# Sheet2.net
KiCad netlist of a schematic drawn in Altium Designer
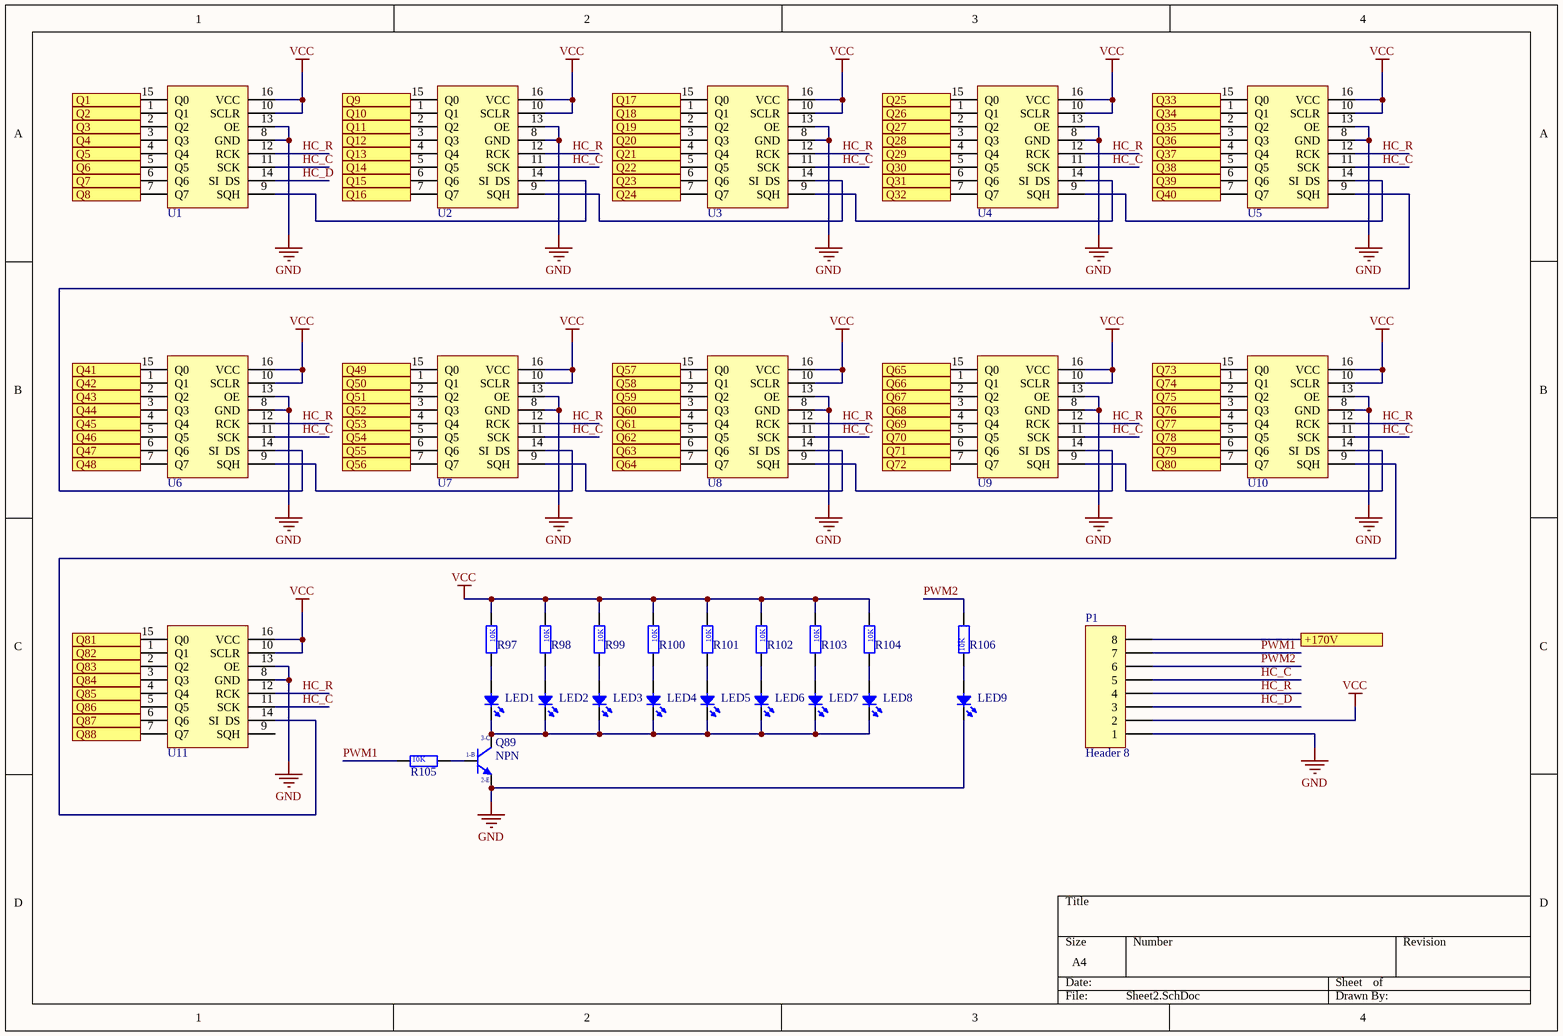
[diagram p0: Sheet2.SchDoc]

(export (version "E")
  (design (tool "Eeschema 10.0.6"))
  (components
    (comp (ref "LED1")
      (value "LED")
      (footprint "0805D")
      (fields (field (name "PUBLISHER") "Altium Limited"))
      (libsource (lib "吴原理图库") (part "LED"))
    )
    (comp (ref "LED2")
      (value "LED")
      (footprint "0805D")
      (fields (field (name "PUBLISHER") "Altium Limited"))
      (libsource (lib "吴原理图库") (part "LED"))
    )
    (comp (ref "LED3")
      (value "LED")
      (footprint "0805D")
      (fields (field (name "PUBLISHER") "Altium Limited"))
      (libsource (lib "吴原理图库") (part "LED"))
    )
    (comp (ref "LED4")
      (value "LED")
      (footprint "0805D")
      (fields (field (name "PUBLISHER") "Altium Limited"))
      (libsource (lib "吴原理图库") (part "LED"))
    )
    (comp (ref "LED5")
      (value "LED")
      (footprint "0805D")
      (fields (field (name "PUBLISHER") "Altium Limited"))
      (libsource (lib "吴原理图库") (part "LED"))
    )
    (comp (ref "LED6")
      (value "LED")
      (footprint "0805D")
      (fields (field (name "PUBLISHER") "Altium Limited"))
      (libsource (lib "吴原理图库") (part "LED"))
    )
    (comp (ref "LED7")
      (value "LED")
      (footprint "0805D")
      (fields (field (name "PUBLISHER") "Altium Limited"))
      (libsource (lib "吴原理图库") (part "LED"))
    )
    (comp (ref "LED8")
      (value "LED")
      (footprint "0805D")
      (fields (field (name "PUBLISHER") "Altium Limited"))
      (libsource (lib "吴原理图库") (part "LED"))
    )
    (comp (ref "LED9")
      (value "LED")
      (footprint "0805D")
      (fields (field (name "PUBLISHER") "Altium Limited"))
      (libsource (lib "吴原理图库") (part "LED"))
    )
    (comp (ref "P1")
      (value "Header 8")
      (footprint "HDR1X8")
      (description "Header, 8-Pin")
      (fields (field (name "PUBLISHER") "Altium Limited"))
      (libsource (lib "Miscellaneous Connectors") (part "Header 8"))
    )
    (comp (ref "Q89") (value "NPN") (footprint "SOT-23") (libsource (lib "吴原理图库") (part "NPN-S8050-SOT-23")))
    (comp (ref "R97")
      (value "10K")
      (footprint "0805")
      (fields (field (name "Comment") "R"))
      (libsource (lib "吴原理图库") (part "R"))
    )
    (comp (ref "R98")
      (value "10K")
      (footprint "0805")
      (fields (field (name "Comment") "R"))
      (libsource (lib "吴原理图库") (part "R"))
    )
    (comp (ref "R99")
      (value "10K")
      (footprint "0805")
      (fields (field (name "Comment") "R"))
      (libsource (lib "吴原理图库") (part "R"))
    )
    (comp (ref "R100")
      (value "10K")
      (footprint "0805")
      (fields (field (name "Comment") "R"))
      (libsource (lib "吴原理图库") (part "R"))
    )
    (comp (ref "R101")
      (value "10K")
      (footprint "0805")
      (fields (field (name "Comment") "R"))
      (libsource (lib "吴原理图库") (part "R"))
    )
    (comp (ref "R102")
      (value "10K")
      (footprint "0805")
      (fields (field (name "Comment") "R"))
      (libsource (lib "吴原理图库") (part "R"))
    )
    (comp (ref "R103")
      (value "10K")
      (footprint "0805")
      (fields (field (name "Comment") "R"))
      (libsource (lib "吴原理图库") (part "R"))
    )
    (comp (ref "R104")
      (value "10K")
      (footprint "0805")
      (fields (field (name "Comment") "R"))
      (libsource (lib "吴原理图库") (part "R"))
    )
    (comp (ref "R105")
      (value "10K")
      (footprint "0805")
      (fields (field (name "Comment") "R"))
      (libsource (lib "") (part "R_1"))
    )
    (comp (ref "R106")
      (value "10K")
      (footprint "0805")
      (fields (field (name "Comment") "R"))
      (libsource (lib "") (part "R_2"))
    )
    (comp (ref "U1") (value "74HC595") (footprint "SOP-16") (libsource (lib "吴原理图库") (part "74HC595_1")))
    (comp (ref "U2") (value "74HC595") (footprint "SOP-16") (libsource (lib "吴原理图库") (part "74HC595_1")))
    (comp (ref "U3") (value "74HC595") (footprint "SOP-16") (libsource (lib "吴原理图库") (part "74HC595_1")))
    (comp (ref "U4") (value "74HC595") (footprint "SOP-16") (libsource (lib "吴原理图库") (part "74HC595_1")))
    (comp (ref "U5") (value "74HC595") (footprint "SOP-16") (libsource (lib "吴原理图库") (part "74HC595_1")))
    (comp (ref "U6") (value "74HC595") (footprint "SOP-16") (libsource (lib "吴原理图库") (part "74HC595_1")))
    (comp (ref "U7") (value "74HC595") (footprint "SOP-16") (libsource (lib "吴原理图库") (part "74HC595_1")))
    (comp (ref "U8") (value "74HC595") (footprint "SOP-16") (libsource (lib "吴原理图库") (part "74HC595_1")))
    (comp (ref "U9") (value "74HC595") (footprint "SOP-16") (libsource (lib "吴原理图库") (part "74HC595_1")))
    (comp (ref "U10") (value "74HC595") (footprint "SOP-16") (libsource (lib "吴原理图库") (part "74HC595_1")))
    (comp (ref "U11") (value "74HC595") (footprint "SOP-16") (libsource (lib "吴原理图库") (part "74HC595_1")))
  )
  (nets
    (net (code "1") (name "/+170V") (class "Default")
      (node (ref "P1") (pin "8") (pinfunction "8_8") (pintype "passive"))
    )
    (net (code "2") (name "/HC_C") (class "Default")
      (node (ref "P1") (pin "5") (pinfunction "5_5") (pintype "passive"))
      (node (ref "U1") (pin "11") (pinfunction "SCK_11") (pintype "power_in"))
      (node (ref "U10") (pin "11") (pinfunction "SCK_11") (pintype "power_in"))
      (node (ref "U11") (pin "11") (pinfunction "SCK_11") (pintype "power_in"))
      (node (ref "U2") (pin "11") (pinfunction "SCK_11") (pintype "power_in"))
      (node (ref "U3") (pin "11") (pinfunction "SCK_11") (pintype "power_in"))
      (node (ref "U4") (pin "11") (pinfunction "SCK_11") (pintype "power_in"))
      (node (ref "U5") (pin "11") (pinfunction "SCK_11") (pintype "power_in"))
      (node (ref "U6") (pin "11") (pinfunction "SCK_11") (pintype "power_in"))
      (node (ref "U7") (pin "11") (pinfunction "SCK_11") (pintype "power_in"))
      (node (ref "U8") (pin "11") (pinfunction "SCK_11") (pintype "power_in"))
      (node (ref "U9") (pin "11") (pinfunction "SCK_11") (pintype "power_in"))
    )
    (net (code "3") (name "/HC_D") (class "Default")
      (node (ref "P1") (pin "3") (pinfunction "3_3") (pintype "passive"))
      (node (ref "U1") (pin "14") (pinfunction "SI__DS_14") (pintype "power_in"))
    )
    (net (code "4") (name "/HC_R") (class "Default")
      (node (ref "P1") (pin "4") (pinfunction "4_4") (pintype "passive"))
      (node (ref "U1") (pin "12") (pinfunction "RCK_12") (pintype "power_in"))
      (node (ref "U10") (pin "12") (pinfunction "RCK_12") (pintype "power_in"))
      (node (ref "U11") (pin "12") (pinfunction "RCK_12") (pintype "power_in"))
      (node (ref "U2") (pin "12") (pinfunction "RCK_12") (pintype "power_in"))
      (node (ref "U3") (pin "12") (pinfunction "RCK_12") (pintype "power_in"))
      (node (ref "U4") (pin "12") (pinfunction "RCK_12") (pintype "power_in"))
      (node (ref "U5") (pin "12") (pinfunction "RCK_12") (pintype "power_in"))
      (node (ref "U6") (pin "12") (pinfunction "RCK_12") (pintype "power_in"))
      (node (ref "U7") (pin "12") (pinfunction "RCK_12") (pintype "power_in"))
      (node (ref "U8") (pin "12") (pinfunction "RCK_12") (pintype "power_in"))
      (node (ref "U9") (pin "12") (pinfunction "RCK_12") (pintype "power_in"))
    )
    (net (code "5") (name "/PWM1") (class "Default")
      (node (ref "P1") (pin "7") (pinfunction "7_7") (pintype "passive"))
      (node (ref "R105") (pin "1") (pinfunction "1_1") (pintype "passive"))
    )
    (net (code "6") (name "/PWM2") (class "Default")
      (node (ref "P1") (pin "6") (pinfunction "6_6") (pintype "passive"))
      (node (ref "R106") (pin "2") (pinfunction "2_2") (pintype "passive"))
    )
    (net (code "7") (name "/Q1") (class "Default")
      (node (ref "U1") (pin "15") (pinfunction "Q0_15") (pintype "power_in"))
    )
    (net (code "8") (name "/Q2") (class "Default")
      (node (ref "U1") (pin "1") (pinfunction "Q1_1") (pintype "power_in"))
    )
    (net (code "9") (name "/Q3") (class "Default")
      (node (ref "U1") (pin "2") (pinfunction "Q2_2") (pintype "power_in"))
    )
    (net (code "10") (name "/Q4") (class "Default")
      (node (ref "U1") (pin "3") (pinfunction "Q3_3") (pintype "power_in"))
    )
    (net (code "11") (name "/Q5") (class "Default")
      (node (ref "U1") (pin "4") (pinfunction "Q4_4") (pintype "power_in"))
    )
    (net (code "12") (name "/Q6") (class "Default")
      (node (ref "U1") (pin "5") (pinfunction "Q5_5") (pintype "power_in"))
    )
    (net (code "13") (name "/Q7") (class "Default")
      (node (ref "U1") (pin "6") (pinfunction "Q6_6") (pintype "power_in"))
    )
    (net (code "14") (name "/Q8") (class "Default")
      (node (ref "U1") (pin "7") (pinfunction "Q7_7") (pintype "power_in"))
    )
    (net (code "15") (name "/Q9") (class "Default")
      (node (ref "U2") (pin "15") (pinfunction "Q0_15") (pintype "power_in"))
    )
    (net (code "16") (name "/Q10") (class "Default")
      (node (ref "U2") (pin "1") (pinfunction "Q1_1") (pintype "power_in"))
    )
    (net (code "17") (name "/Q11") (class "Default")
      (node (ref "U2") (pin "2") (pinfunction "Q2_2") (pintype "power_in"))
    )
    (net (code "18") (name "/Q12") (class "Default")
      (node (ref "U2") (pin "3") (pinfunction "Q3_3") (pintype "power_in"))
    )
    (net (code "19") (name "/Q13") (class "Default")
      (node (ref "U2") (pin "4") (pinfunction "Q4_4") (pintype "power_in"))
    )
    (net (code "20") (name "/Q14") (class "Default")
      (node (ref "U2") (pin "5") (pinfunction "Q5_5") (pintype "power_in"))
    )
    (net (code "21") (name "/Q15") (class "Default")
      (node (ref "U2") (pin "6") (pinfunction "Q6_6") (pintype "power_in"))
    )
    (net (code "22") (name "/Q16") (class "Default")
      (node (ref "U2") (pin "7") (pinfunction "Q7_7") (pintype "power_in"))
    )
    (net (code "23") (name "/Q17") (class "Default")
      (node (ref "U3") (pin "15") (pinfunction "Q0_15") (pintype "power_in"))
    )
    (net (code "24") (name "/Q18") (class "Default")
      (node (ref "U3") (pin "1") (pinfunction "Q1_1") (pintype "power_in"))
    )
    (net (code "25") (name "/Q19") (class "Default")
      (node (ref "U3") (pin "2") (pinfunction "Q2_2") (pintype "power_in"))
    )
    (net (code "26") (name "/Q20") (class "Default")
      (node (ref "U3") (pin "3") (pinfunction "Q3_3") (pintype "power_in"))
    )
    (net (code "27") (name "/Q21") (class "Default")
      (node (ref "U3") (pin "4") (pinfunction "Q4_4") (pintype "power_in"))
    )
    (net (code "28") (name "/Q22") (class "Default")
      (node (ref "U3") (pin "5") (pinfunction "Q5_5") (pintype "power_in"))
    )
    (net (code "29") (name "/Q23") (class "Default")
      (node (ref "U3") (pin "6") (pinfunction "Q6_6") (pintype "power_in"))
    )
    (net (code "30") (name "/Q24") (class "Default")
      (node (ref "U3") (pin "7") (pinfunction "Q7_7") (pintype "power_in"))
    )
    (net (code "31") (name "/Q25") (class "Default")
      (node (ref "U4") (pin "15") (pinfunction "Q0_15") (pintype "power_in"))
    )
    (net (code "32") (name "/Q26") (class "Default")
      (node (ref "U4") (pin "1") (pinfunction "Q1_1") (pintype "power_in"))
    )
    (net (code "33") (name "/Q27") (class "Default")
      (node (ref "U4") (pin "2") (pinfunction "Q2_2") (pintype "power_in"))
    )
    (net (code "34") (name "/Q28") (class "Default")
      (node (ref "U4") (pin "3") (pinfunction "Q3_3") (pintype "power_in"))
    )
    (net (code "35") (name "/Q29") (class "Default")
      (node (ref "U4") (pin "4") (pinfunction "Q4_4") (pintype "power_in"))
    )
    (net (code "36") (name "/Q30") (class "Default")
      (node (ref "U4") (pin "5") (pinfunction "Q5_5") (pintype "power_in"))
    )
    (net (code "37") (name "/Q31") (class "Default")
      (node (ref "U4") (pin "6") (pinfunction "Q6_6") (pintype "power_in"))
    )
    (net (code "38") (name "/Q32") (class "Default")
      (node (ref "U4") (pin "7") (pinfunction "Q7_7") (pintype "power_in"))
    )
    (net (code "39") (name "/Q33") (class "Default")
      (node (ref "U5") (pin "15") (pinfunction "Q0_15") (pintype "power_in"))
    )
    (net (code "40") (name "/Q34") (class "Default")
      (node (ref "U5") (pin "1") (pinfunction "Q1_1") (pintype "power_in"))
    )
    (net (code "41") (name "/Q35") (class "Default")
      (node (ref "U5") (pin "2") (pinfunction "Q2_2") (pintype "power_in"))
    )
    (net (code "42") (name "/Q36") (class "Default")
      (node (ref "U5") (pin "3") (pinfunction "Q3_3") (pintype "power_in"))
    )
    (net (code "43") (name "/Q37") (class "Default")
      (node (ref "U5") (pin "4") (pinfunction "Q4_4") (pintype "power_in"))
    )
    (net (code "44") (name "/Q38") (class "Default")
      (node (ref "U5") (pin "5") (pinfunction "Q5_5") (pintype "power_in"))
    )
    (net (code "45") (name "/Q39") (class "Default")
      (node (ref "U5") (pin "6") (pinfunction "Q6_6") (pintype "power_in"))
    )
    (net (code "46") (name "/Q40") (class "Default")
      (node (ref "U5") (pin "7") (pinfunction "Q7_7") (pintype "power_in"))
    )
    (net (code "47") (name "/Q41") (class "Default")
      (node (ref "U6") (pin "15") (pinfunction "Q0_15") (pintype "power_in"))
    )
    (net (code "48") (name "/Q42") (class "Default")
      (node (ref "U6") (pin "1") (pinfunction "Q1_1") (pintype "power_in"))
    )
    (net (code "49") (name "/Q43") (class "Default")
      (node (ref "U6") (pin "2") (pinfunction "Q2_2") (pintype "power_in"))
    )
    (net (code "50") (name "/Q44") (class "Default")
      (node (ref "U6") (pin "3") (pinfunction "Q3_3") (pintype "power_in"))
    )
    (net (code "51") (name "/Q45") (class "Default")
      (node (ref "U6") (pin "4") (pinfunction "Q4_4") (pintype "power_in"))
    )
    (net (code "52") (name "/Q46") (class "Default")
      (node (ref "U6") (pin "5") (pinfunction "Q5_5") (pintype "power_in"))
    )
    (net (code "53") (name "/Q47") (class "Default")
      (node (ref "U6") (pin "6") (pinfunction "Q6_6") (pintype "power_in"))
    )
    (net (code "54") (name "/Q48") (class "Default")
      (node (ref "U6") (pin "7") (pinfunction "Q7_7") (pintype "power_in"))
    )
    (net (code "55") (name "/Q49") (class "Default")
      (node (ref "U7") (pin "15") (pinfunction "Q0_15") (pintype "power_in"))
    )
    (net (code "56") (name "/Q50") (class "Default")
      (node (ref "U7") (pin "1") (pinfunction "Q1_1") (pintype "power_in"))
    )
    (net (code "57") (name "/Q51") (class "Default")
      (node (ref "U7") (pin "2") (pinfunction "Q2_2") (pintype "power_in"))
    )
    (net (code "58") (name "/Q52") (class "Default")
      (node (ref "U7") (pin "3") (pinfunction "Q3_3") (pintype "power_in"))
    )
    (net (code "59") (name "/Q53") (class "Default")
      (node (ref "U7") (pin "4") (pinfunction "Q4_4") (pintype "power_in"))
    )
    (net (code "60") (name "/Q54") (class "Default")
      (node (ref "U7") (pin "5") (pinfunction "Q5_5") (pintype "power_in"))
    )
    (net (code "61") (name "/Q55") (class "Default")
      (node (ref "U7") (pin "6") (pinfunction "Q6_6") (pintype "power_in"))
    )
    (net (code "62") (name "/Q56") (class "Default")
      (node (ref "U7") (pin "7") (pinfunction "Q7_7") (pintype "power_in"))
    )
    (net (code "63") (name "/Q57") (class "Default")
      (node (ref "U8") (pin "15") (pinfunction "Q0_15") (pintype "power_in"))
    )
    (net (code "64") (name "/Q58") (class "Default")
      (node (ref "U8") (pin "1") (pinfunction "Q1_1") (pintype "power_in"))
    )
    (net (code "65") (name "/Q59") (class "Default")
      (node (ref "U8") (pin "2") (pinfunction "Q2_2") (pintype "power_in"))
    )
    (net (code "66") (name "/Q60") (class "Default")
      (node (ref "U8") (pin "3") (pinfunction "Q3_3") (pintype "power_in"))
    )
    (net (code "67") (name "/Q61") (class "Default")
      (node (ref "U8") (pin "4") (pinfunction "Q4_4") (pintype "power_in"))
    )
    (net (code "68") (name "/Q62") (class "Default")
      (node (ref "U8") (pin "5") (pinfunction "Q5_5") (pintype "power_in"))
    )
    (net (code "69") (name "/Q63") (class "Default")
      (node (ref "U8") (pin "6") (pinfunction "Q6_6") (pintype "power_in"))
    )
    (net (code "70") (name "/Q64") (class "Default")
      (node (ref "U8") (pin "7") (pinfunction "Q7_7") (pintype "power_in"))
    )
    (net (code "71") (name "/Q65") (class "Default")
      (node (ref "U9") (pin "15") (pinfunction "Q0_15") (pintype "power_in"))
    )
    (net (code "72") (name "/Q66") (class "Default")
      (node (ref "U9") (pin "1") (pinfunction "Q1_1") (pintype "power_in"))
    )
    (net (code "73") (name "/Q67") (class "Default")
      (node (ref "U9") (pin "2") (pinfunction "Q2_2") (pintype "power_in"))
    )
    (net (code "74") (name "/Q68") (class "Default")
      (node (ref "U9") (pin "3") (pinfunction "Q3_3") (pintype "power_in"))
    )
    (net (code "75") (name "/Q69") (class "Default")
      (node (ref "U9") (pin "4") (pinfunction "Q4_4") (pintype "power_in"))
    )
    (net (code "76") (name "/Q70") (class "Default")
      (node (ref "U9") (pin "5") (pinfunction "Q5_5") (pintype "power_in"))
    )
    (net (code "77") (name "/Q71") (class "Default")
      (node (ref "U9") (pin "6") (pinfunction "Q6_6") (pintype "power_in"))
    )
    (net (code "78") (name "/Q72") (class "Default")
      (node (ref "U9") (pin "7") (pinfunction "Q7_7") (pintype "power_in"))
    )
    (net (code "79") (name "/Q73") (class "Default")
      (node (ref "U10") (pin "15") (pinfunction "Q0_15") (pintype "power_in"))
    )
    (net (code "80") (name "/Q74") (class "Default")
      (node (ref "U10") (pin "1") (pinfunction "Q1_1") (pintype "power_in"))
    )
    (net (code "81") (name "/Q75") (class "Default")
      (node (ref "U10") (pin "2") (pinfunction "Q2_2") (pintype "power_in"))
    )
    (net (code "82") (name "/Q76") (class "Default")
      (node (ref "U10") (pin "3") (pinfunction "Q3_3") (pintype "power_in"))
    )
    (net (code "83") (name "/Q77") (class "Default")
      (node (ref "U10") (pin "4") (pinfunction "Q4_4") (pintype "power_in"))
    )
    (net (code "84") (name "/Q78") (class "Default")
      (node (ref "U10") (pin "5") (pinfunction "Q5_5") (pintype "power_in"))
    )
    (net (code "85") (name "/Q79") (class "Default")
      (node (ref "U10") (pin "6") (pinfunction "Q6_6") (pintype "power_in"))
    )
    (net (code "86") (name "/Q80") (class "Default")
      (node (ref "U10") (pin "7") (pinfunction "Q7_7") (pintype "power_in"))
    )
    (net (code "87") (name "/Q81") (class "Default")
      (node (ref "U11") (pin "15") (pinfunction "Q0_15") (pintype "power_in"))
    )
    (net (code "88") (name "/Q82") (class "Default")
      (node (ref "U11") (pin "1") (pinfunction "Q1_1") (pintype "power_in"))
    )
    (net (code "89") (name "/Q83") (class "Default")
      (node (ref "U11") (pin "2") (pinfunction "Q2_2") (pintype "power_in"))
    )
    (net (code "90") (name "/Q84") (class "Default")
      (node (ref "U11") (pin "3") (pinfunction "Q3_3") (pintype "power_in"))
    )
    (net (code "91") (name "/Q85") (class "Default")
      (node (ref "U11") (pin "4") (pinfunction "Q4_4") (pintype "power_in"))
    )
    (net (code "92") (name "/Q86") (class "Default")
      (node (ref "U11") (pin "5") (pinfunction "Q5_5") (pintype "power_in"))
    )
    (net (code "93") (name "/Q87") (class "Default")
      (node (ref "U11") (pin "6") (pinfunction "Q6_6") (pintype "power_in"))
    )
    (net (code "94") (name "/Q88") (class "Default")
      (node (ref "U11") (pin "7") (pinfunction "Q7_7") (pintype "power_in"))
    )
    (net (code "95") (name "GND") (class "Default")
      (node (ref "LED9") (pin "2") (pinfunction "K_2") (pintype "passive"))
      (node (ref "P1") (pin "1") (pinfunction "1_1") (pintype "passive"))
      (node (ref "Q89") (pin "2") (pinfunction "E_2") (pintype "passive"))
      (node (ref "U1") (pin "13") (pinfunction "OE_13") (pintype "power_in"))
      (node (ref "U1") (pin "8") (pinfunction "GND_8") (pintype "power_in"))
      (node (ref "U10") (pin "13") (pinfunction "OE_13") (pintype "power_in"))
      (node (ref "U10") (pin "8") (pinfunction "GND_8") (pintype "power_in"))
      (node (ref "U11") (pin "13") (pinfunction "OE_13") (pintype "power_in"))
      (node (ref "U11") (pin "8") (pinfunction "GND_8") (pintype "power_in"))
      (node (ref "U2") (pin "13") (pinfunction "OE_13") (pintype "power_in"))
      (node (ref "U2") (pin "8") (pinfunction "GND_8") (pintype "power_in"))
      (node (ref "U3") (pin "13") (pinfunction "OE_13") (pintype "power_in"))
      (node (ref "U3") (pin "8") (pinfunction "GND_8") (pintype "power_in"))
      (node (ref "U4") (pin "13") (pinfunction "OE_13") (pintype "power_in"))
      (node (ref "U4") (pin "8") (pinfunction "GND_8") (pintype "power_in"))
      (node (ref "U5") (pin "13") (pinfunction "OE_13") (pintype "power_in"))
      (node (ref "U5") (pin "8") (pinfunction "GND_8") (pintype "power_in"))
      (node (ref "U6") (pin "13") (pinfunction "OE_13") (pintype "power_in"))
      (node (ref "U6") (pin "8") (pinfunction "GND_8") (pintype "power_in"))
      (node (ref "U7") (pin "13") (pinfunction "OE_13") (pintype "power_in"))
      (node (ref "U7") (pin "8") (pinfunction "GND_8") (pintype "power_in"))
      (node (ref "U8") (pin "13") (pinfunction "OE_13") (pintype "power_in"))
      (node (ref "U8") (pin "8") (pinfunction "GND_8") (pintype "power_in"))
      (node (ref "U9") (pin "13") (pinfunction "OE_13") (pintype "power_in"))
      (node (ref "U9") (pin "8") (pinfunction "GND_8") (pintype "power_in"))
    )
    (net (code "96") (name "Net-(LED1-A)") (class "Default")
      (node (ref "LED1") (pin "1") (pinfunction "A_1") (pintype "passive"))
      (node (ref "R97") (pin "2") (pinfunction "2_2") (pintype "passive"))
    )
    (net (code "97") (name "Net-(LED1-K)") (class "Default")
      (node (ref "LED1") (pin "2") (pinfunction "K_2") (pintype "passive"))
      (node (ref "LED2") (pin "2") (pinfunction "K_2") (pintype "passive"))
      (node (ref "LED3") (pin "2") (pinfunction "K_2") (pintype "passive"))
      (node (ref "LED4") (pin "2") (pinfunction "K_2") (pintype "passive"))
      (node (ref "LED5") (pin "2") (pinfunction "K_2") (pintype "passive"))
      (node (ref "LED6") (pin "2") (pinfunction "K_2") (pintype "passive"))
      (node (ref "LED7") (pin "2") (pinfunction "K_2") (pintype "passive"))
      (node (ref "LED8") (pin "2") (pinfunction "K_2") (pintype "passive"))
      (node (ref "Q89") (pin "3") (pinfunction "C_3") (pintype "passive"))
    )
    (net (code "98") (name "Net-(LED2-A)") (class "Default")
      (node (ref "LED2") (pin "1") (pinfunction "A_1") (pintype "passive"))
      (node (ref "R98") (pin "2") (pinfunction "2_2") (pintype "passive"))
    )
    (net (code "99") (name "Net-(LED3-A)") (class "Default")
      (node (ref "LED3") (pin "1") (pinfunction "A_1") (pintype "passive"))
      (node (ref "R99") (pin "2") (pinfunction "2_2") (pintype "passive"))
    )
    (net (code "100") (name "Net-(LED4-A)") (class "Default")
      (node (ref "LED4") (pin "1") (pinfunction "A_1") (pintype "passive"))
      (node (ref "R100") (pin "2") (pinfunction "2_2") (pintype "passive"))
    )
    (net (code "101") (name "Net-(LED5-A)") (class "Default")
      (node (ref "LED5") (pin "1") (pinfunction "A_1") (pintype "passive"))
      (node (ref "R101") (pin "2") (pinfunction "2_2") (pintype "passive"))
    )
    (net (code "102") (name "Net-(LED6-A)") (class "Default")
      (node (ref "LED6") (pin "1") (pinfunction "A_1") (pintype "passive"))
      (node (ref "R102") (pin "2") (pinfunction "2_2") (pintype "passive"))
    )
    (net (code "103") (name "Net-(LED7-A)") (class "Default")
      (node (ref "LED7") (pin "1") (pinfunction "A_1") (pintype "passive"))
      (node (ref "R103") (pin "2") (pinfunction "2_2") (pintype "passive"))
    )
    (net (code "104") (name "Net-(LED8-A)") (class "Default")
      (node (ref "LED8") (pin "1") (pinfunction "A_1") (pintype "passive"))
      (node (ref "R104") (pin "2") (pinfunction "2_2") (pintype "passive"))
    )
    (net (code "105") (name "Net-(LED9-A)") (class "Default")
      (node (ref "LED9") (pin "1") (pinfunction "A_1") (pintype "passive"))
      (node (ref "R106") (pin "1") (pinfunction "1_1") (pintype "passive"))
    )
    (net (code "106") (name "Net-(Q89-B)") (class "Default")
      (node (ref "Q89") (pin "1") (pinfunction "B_1") (pintype "passive"))
      (node (ref "R105") (pin "2") (pinfunction "2_2") (pintype "passive"))
    )
    (net (code "107") (name "Net-(U1-SQH)") (class "Default")
      (node (ref "U1") (pin "9") (pinfunction "SQH_9") (pintype "power_in"))
      (node (ref "U2") (pin "14") (pinfunction "SI__DS_14") (pintype "power_in"))
    )
    (net (code "108") (name "Net-(U2-SQH)") (class "Default")
      (node (ref "U2") (pin "9") (pinfunction "SQH_9") (pintype "power_in"))
      (node (ref "U3") (pin "14") (pinfunction "SI__DS_14") (pintype "power_in"))
    )
    (net (code "109") (name "Net-(U3-SQH)") (class "Default")
      (node (ref "U3") (pin "9") (pinfunction "SQH_9") (pintype "power_in"))
      (node (ref "U4") (pin "14") (pinfunction "SI__DS_14") (pintype "power_in"))
    )
    (net (code "110") (name "Net-(U4-SQH)") (class "Default")
      (node (ref "U4") (pin "9") (pinfunction "SQH_9") (pintype "power_in"))
      (node (ref "U5") (pin "14") (pinfunction "SI__DS_14") (pintype "power_in"))
    )
    (net (code "111") (name "Net-(U5-SQH)") (class "Default")
      (node (ref "U5") (pin "9") (pinfunction "SQH_9") (pintype "power_in"))
      (node (ref "U6") (pin "14") (pinfunction "SI__DS_14") (pintype "power_in"))
    )
    (net (code "112") (name "Net-(U6-SQH)") (class "Default")
      (node (ref "U6") (pin "9") (pinfunction "SQH_9") (pintype "power_in"))
      (node (ref "U7") (pin "14") (pinfunction "SI__DS_14") (pintype "power_in"))
    )
    (net (code "113") (name "Net-(U7-SQH)") (class "Default")
      (node (ref "U7") (pin "9") (pinfunction "SQH_9") (pintype "power_in"))
      (node (ref "U8") (pin "14") (pinfunction "SI__DS_14") (pintype "power_in"))
    )
    (net (code "114") (name "Net-(U8-SQH)") (class "Default")
      (node (ref "U8") (pin "9") (pinfunction "SQH_9") (pintype "power_in"))
      (node (ref "U9") (pin "14") (pinfunction "SI__DS_14") (pintype "power_in"))
    )
    (net (code "115") (name "Net-(U10-SI__DS)") (class "Default")
      (node (ref "U10") (pin "14") (pinfunction "SI__DS_14") (pintype "power_in"))
      (node (ref "U9") (pin "9") (pinfunction "SQH_9") (pintype "power_in"))
    )
    (net (code "116") (name "Net-(U10-SQH)") (class "Default")
      (node (ref "U10") (pin "9") (pinfunction "SQH_9") (pintype "power_in"))
      (node (ref "U11") (pin "14") (pinfunction "SI__DS_14") (pintype "power_in"))
    )
    (net (code "117") (name "VCC") (class "Default")
      (node (ref "P1") (pin "2") (pinfunction "2_2") (pintype "passive"))
      (node (ref "R100") (pin "1") (pinfunction "1_1") (pintype "passive"))
      (node (ref "R101") (pin "1") (pinfunction "1_1") (pintype "passive"))
      (node (ref "R102") (pin "1") (pinfunction "1_1") (pintype "passive"))
      (node (ref "R103") (pin "1") (pinfunction "1_1") (pintype "passive"))
      (node (ref "R104") (pin "1") (pinfunction "1_1") (pintype "passive"))
      (node (ref "R97") (pin "1") (pinfunction "1_1") (pintype "passive"))
      (node (ref "R98") (pin "1") (pinfunction "1_1") (pintype "passive"))
      (node (ref "R99") (pin "1") (pinfunction "1_1") (pintype "passive"))
      (node (ref "U1") (pin "10") (pinfunction "SCLR_10") (pintype "power_in"))
      (node (ref "U1") (pin "16") (pinfunction "VCC_16") (pintype "passive"))
      (node (ref "U10") (pin "10") (pinfunction "SCLR_10") (pintype "power_in"))
      (node (ref "U10") (pin "16") (pinfunction "VCC_16") (pintype "passive"))
      (node (ref "U11") (pin "10") (pinfunction "SCLR_10") (pintype "power_in"))
      (node (ref "U11") (pin "16") (pinfunction "VCC_16") (pintype "passive"))
      (node (ref "U2") (pin "10") (pinfunction "SCLR_10") (pintype "power_in"))
      (node (ref "U2") (pin "16") (pinfunction "VCC_16") (pintype "passive"))
      (node (ref "U3") (pin "10") (pinfunction "SCLR_10") (pintype "power_in"))
      (node (ref "U3") (pin "16") (pinfunction "VCC_16") (pintype "passive"))
      (node (ref "U4") (pin "10") (pinfunction "SCLR_10") (pintype "power_in"))
      (node (ref "U4") (pin "16") (pinfunction "VCC_16") (pintype "passive"))
      (node (ref "U5") (pin "10") (pinfunction "SCLR_10") (pintype "power_in"))
      (node (ref "U5") (pin "16") (pinfunction "VCC_16") (pintype "passive"))
      (node (ref "U6") (pin "10") (pinfunction "SCLR_10") (pintype "power_in"))
      (node (ref "U6") (pin "16") (pinfunction "VCC_16") (pintype "passive"))
      (node (ref "U7") (pin "10") (pinfunction "SCLR_10") (pintype "power_in"))
      (node (ref "U7") (pin "16") (pinfunction "VCC_16") (pintype "passive"))
      (node (ref "U8") (pin "10") (pinfunction "SCLR_10") (pintype "power_in"))
      (node (ref "U8") (pin "16") (pinfunction "VCC_16") (pintype "passive"))
      (node (ref "U9") (pin "10") (pinfunction "SCLR_10") (pintype "power_in"))
      (node (ref "U9") (pin "16") (pinfunction "VCC_16") (pintype "passive"))
    )
    (net (code "118") (name "unconnected-(U11-SQH-Pad9)") (class "Default")
      (node (ref "U11") (pin "9") (pinfunction "SQH_9") (pintype "power_in"))
    )
  )
)
